# clock.net
KiCad netlist of a schematic drawn in EAGLE
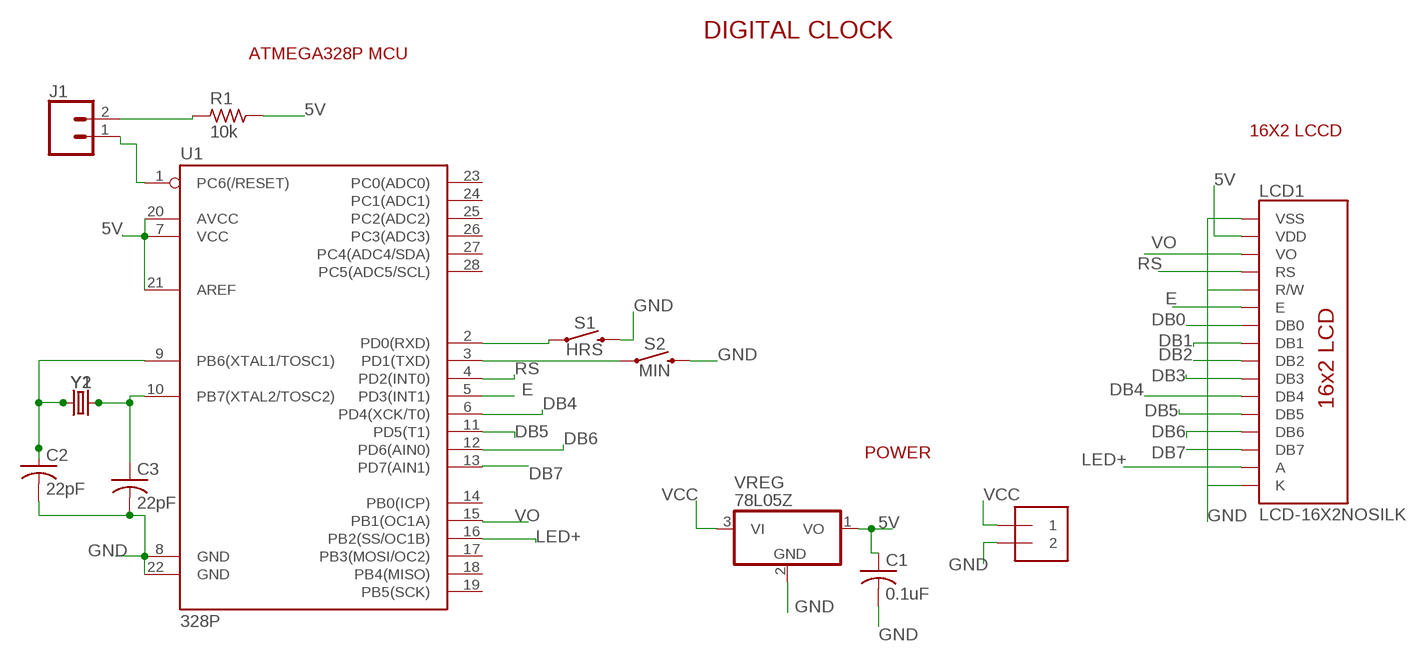
[diagram p0: schematic, sheet 1]

(export (version "E")
  (design (tool "Eeschema 10.0.6"))
  (components
    (comp (ref "C1")
      (value "0.1uF")
      (footprint "eagle-import:C1206")
      (libsource (lib "eagle-import") (part "C-USC1206"))
    )
    (comp (ref "C2")
      (value "22pF")
      (footprint "eagle-import:C1206")
      (libsource (lib "eagle-import") (part "C-USC1206"))
    )
    (comp (ref "C3")
      (value "22pF")
      (footprint "eagle-import:C1206")
      (libsource (lib "eagle-import") (part "C-USC1206"))
    )
    (comp (ref "J1")
      (value "CONN_02")
      (footprint "eagle-import:1X02")
      (libsource (lib "eagle-import") (part "CONN_02"))
    )
    (comp (ref "LCD1")
      (value "LCD-16X2NOSILK")
      (footprint "eagle-import:LCD-16X2_NOSILK")
      (libsource (lib "eagle-import") (part "LCD-16X2NOSILK"))
    )
    (comp (ref "POWER")
      (value "1X2-3.5MM")
      (footprint "eagle-import:1X2-3.5MM")
      (libsource (lib "eagle-import") (part "1X2-3.5MM"))
    )
    (comp (ref "R1")
      (value "10k")
      (footprint "eagle-import:R1206")
      (libsource (lib "eagle-import") (part "R_1206"))
    )
    (comp (ref "S1")
      (value "HRS")
      (footprint "eagle-import:TACTILE_SWITCH_PTH_6.0MM")
      (libsource (lib "eagle-import") (part "MOMENTARY-SWITCH-SPST-PTH-6.0MM"))
    )
    (comp (ref "S2")
      (value "MIN")
      (footprint "eagle-import:TACTILE_SWITCH_PTH_6.0MM")
      (libsource (lib "eagle-import") (part "MOMENTARY-SWITCH-SPST-PTH-6.0MM"))
    )
    (comp (ref "U1")
      (value "328P")
      (footprint "eagle-import:DIP28")
      (libsource (lib "eagle-import") (part "ATMEGA328P_PDIP"))
    )
    (comp (ref "VREG")
      (value "78L05Z")
      (footprint "eagle-import:TO92")
      (libsource (lib "eagle-import") (part "78ZL05"))
    )
    (comp (ref "Y1")
      (value "CRYSTALPTH-HC49US")
      (footprint "eagle-import:HC49US")
      (libsource (lib "eagle-import") (part "CRYSTALPTH-HC49US"))
    )
    (comp (ref "Y2")
      (value "CRYSTALPTH-HC49US")
      (footprint "eagle-import:HC49US")
      (libsource (lib "eagle-import") (part "CRYSTALPTH-HC49US"))
    )
  )
  (nets
    (net (code "1") (name "/5V") (class "Default")
      (node (ref "C1") (pin "1") (pinfunction "1_1") (pintype "passive"))
      (node (ref "LCD1") (pin "2") (pinfunction "VDD_2") (pintype "power_in"))
      (node (ref "R1") (pin "2") (pinfunction "2_2") (pintype "passive"))
      (node (ref "U1") (pin "20") (pinfunction "AVCC_20") (pintype "bidirectional"))
      (node (ref "U1") (pin "21") (pinfunction "AREF_21") (pintype "bidirectional"))
      (node (ref "U1") (pin "7") (pinfunction "VCC_7") (pintype "bidirectional"))
      (node (ref "VREG") (pin "1") (pinfunction "VO_1") (pintype "passive"))
    )
    (net (code "2") (name "/DB0") (class "Default")
      (node (ref "LCD1") (pin "7") (pinfunction "DB0_7") (pintype "bidirectional"))
    )
    (net (code "3") (name "/DB1") (class "Default")
      (node (ref "LCD1") (pin "8") (pinfunction "DB1_8") (pintype "bidirectional"))
    )
    (net (code "4") (name "/DB2") (class "Default")
      (node (ref "LCD1") (pin "9") (pinfunction "DB2_9") (pintype "bidirectional"))
    )
    (net (code "5") (name "/DB3") (class "Default")
      (node (ref "LCD1") (pin "10") (pinfunction "DB3_10") (pintype "bidirectional"))
    )
    (net (code "6") (name "/DB4") (class "Default")
      (node (ref "LCD1") (pin "11") (pinfunction "DB4_11") (pintype "bidirectional"))
      (node (ref "U1") (pin "6") (pinfunction "PD4(XCK/T0)_6") (pintype "bidirectional"))
    )
    (net (code "7") (name "/DB5") (class "Default")
      (node (ref "LCD1") (pin "12") (pinfunction "DB5_12") (pintype "bidirectional"))
      (node (ref "U1") (pin "11") (pinfunction "PD5(T1)_11") (pintype "bidirectional"))
    )
    (net (code "8") (name "/DB6") (class "Default")
      (node (ref "LCD1") (pin "13") (pinfunction "DB6_13") (pintype "bidirectional"))
      (node (ref "U1") (pin "12") (pinfunction "PD6(AIN0)_12") (pintype "bidirectional"))
    )
    (net (code "9") (name "/DB7") (class "Default")
      (node (ref "LCD1") (pin "14") (pinfunction "DB7_14") (pintype "bidirectional"))
      (node (ref "U1") (pin "13") (pinfunction "PD7(AIN1)_13") (pintype "bidirectional"))
    )
    (net (code "10") (name "/E") (class "Default")
      (node (ref "LCD1") (pin "6") (pinfunction "E_6") (pintype "input"))
      (node (ref "U1") (pin "5") (pinfunction "PD3(INT1)_5") (pintype "bidirectional"))
    )
    (net (code "11") (name "/GND") (class "Default")
      (node (ref "C1") (pin "2") (pinfunction "2_2") (pintype "passive"))
      (node (ref "C2") (pin "1") (pinfunction "1_1") (pintype "passive"))
      (node (ref "C2") (pin "2") (pinfunction "2_2") (pintype "passive"))
      (node (ref "C3") (pin "2") (pinfunction "2_2") (pintype "passive"))
      (node (ref "LCD1") (pin "16") (pinfunction "K_16") (pintype "power_in"))
      (node (ref "POWER") (pin "2") (pinfunction "2_2") (pintype "passive"))
      (node (ref "S1") (pin "3") (pinfunction "2_3") (pintype "passive"))
      (node (ref "S2") (pin "3") (pinfunction "2_3") (pintype "passive"))
      (node (ref "U1") (pin "22") (pinfunction "GND_22") (pintype "bidirectional"))
      (node (ref "U1") (pin "8") (pinfunction "GND_8") (pintype "bidirectional"))
      (node (ref "U1") (pin "9") (pinfunction "PB6(XTAL1/TOSC1)_9") (pintype "bidirectional"))
      (node (ref "VREG") (pin "2") (pinfunction "GND_2") (pintype "passive"))
      (node (ref "Y1") (pin "1") (pinfunction "1_1") (pintype "passive"))
      (node (ref "Y2") (pin "1") (pinfunction "1_1") (pintype "passive"))
    )
    (net (code "12") (name "/LED+") (class "Default")
      (node (ref "LCD1") (pin "15") (pinfunction "A_15") (pintype "power_in"))
      (node (ref "U1") (pin "16") (pinfunction "PB2(SS/OC1B)_16") (pintype "bidirectional"))
    )
    (net (code "13") (name "/RS") (class "Default")
      (node (ref "LCD1") (pin "4") (pinfunction "RS_4") (pintype "input"))
      (node (ref "U1") (pin "4") (pinfunction "PD2(INT0)_4") (pintype "bidirectional"))
    )
    (net (code "14") (name "/VCC") (class "Default")
      (node (ref "POWER") (pin "1") (pinfunction "1_1") (pintype "passive"))
      (node (ref "VREG") (pin "3") (pinfunction "VI_3") (pintype "input"))
    )
    (net (code "15") (name "/VO") (class "Default")
      (node (ref "LCD1") (pin "3") (pinfunction "VO_3") (pintype "bidirectional"))
      (node (ref "U1") (pin "15") (pinfunction "PB1(OC1A)_15") (pintype "bidirectional"))
    )
    (net (code "16") (name "Net-(J1-Pad2)") (class "Default")
      (node (ref "J1") (pin "2") (pinfunction "2_2") (pintype "passive"))
      (node (ref "R1") (pin "1") (pinfunction "1_1") (pintype "passive"))
    )
    (net (code "17") (name "Net-(LCD1-R{slash}W)") (class "Default")
      (node (ref "LCD1") (pin "1") (pinfunction "VSS_1") (pintype "power_in"))
      (node (ref "LCD1") (pin "5") (pinfunction "R/W_5") (pintype "input"))
    )
    (net (code "18") (name "Net-(U1-PB7(XTAL2{slash}TOSC2))") (class "Default")
      (node (ref "C3") (pin "1") (pinfunction "1_1") (pintype "passive"))
      (node (ref "U1") (pin "10") (pinfunction "PB7(XTAL2/TOSC2)_10") (pintype "bidirectional"))
      (node (ref "Y1") (pin "2") (pinfunction "2_2") (pintype "passive"))
      (node (ref "Y2") (pin "2") (pinfunction "2_2") (pintype "passive"))
    )
    (net (code "19") (name "Net-(U1-PC6({slash}RESET))") (class "Default")
      (node (ref "J1") (pin "1") (pinfunction "1_1") (pintype "passive"))
      (node (ref "U1") (pin "1") (pinfunction "PC6(/RESET)_1") (pintype "bidirectional"))
    )
    (net (code "20") (name "Net-(U1-PD0(RXD))") (class "Default")
      (node (ref "S1") (pin "1") (pinfunction "1_1") (pintype "passive"))
      (node (ref "U1") (pin "2") (pinfunction "PD0(RXD)_2") (pintype "bidirectional"))
    )
    (net (code "21") (name "Net-(U1-PD1(TXD))") (class "Default")
      (node (ref "S2") (pin "1") (pinfunction "1_1") (pintype "passive"))
      (node (ref "U1") (pin "3") (pinfunction "PD1(TXD)_3") (pintype "bidirectional"))
    )
    (net (code "22") (name "unconnected-(U1-PB0(ICP)-Pad14)") (class "Default")
      (node (ref "U1") (pin "14") (pinfunction "PB0(ICP)_14") (pintype "bidirectional"))
    )
    (net (code "23") (name "unconnected-(U1-PB3(MOSI{slash}OC2)-Pad17)") (class "Default")
      (node (ref "U1") (pin "17") (pinfunction "PB3(MOSI/OC2)_17") (pintype "bidirectional"))
    )
    (net (code "24") (name "unconnected-(U1-PB4(MISO)-Pad18)") (class "Default")
      (node (ref "U1") (pin "18") (pinfunction "PB4(MISO)_18") (pintype "bidirectional"))
    )
    (net (code "25") (name "unconnected-(U1-PB5(SCK)-Pad19)") (class "Default")
      (node (ref "U1") (pin "19") (pinfunction "PB5(SCK)_19") (pintype "bidirectional"))
    )
    (net (code "26") (name "unconnected-(U1-PC0(ADC0)-Pad23)") (class "Default")
      (node (ref "U1") (pin "23") (pinfunction "PC0(ADC0)_23") (pintype "bidirectional"))
    )
    (net (code "27") (name "unconnected-(U1-PC1(ADC1)-Pad24)") (class "Default")
      (node (ref "U1") (pin "24") (pinfunction "PC1(ADC1)_24") (pintype "bidirectional"))
    )
    (net (code "28") (name "unconnected-(U1-PC2(ADC2)-Pad25)") (class "Default")
      (node (ref "U1") (pin "25") (pinfunction "PC2(ADC2)_25") (pintype "bidirectional"))
    )
    (net (code "29") (name "unconnected-(U1-PC3(ADC3)-Pad26)") (class "Default")
      (node (ref "U1") (pin "26") (pinfunction "PC3(ADC3)_26") (pintype "bidirectional"))
    )
    (net (code "30") (name "unconnected-(U1-PC4(ADC4{slash}SDA)-Pad27)") (class "Default")
      (node (ref "U1") (pin "27") (pinfunction "PC4(ADC4/SDA)_27") (pintype "bidirectional"))
    )
    (net (code "31") (name "unconnected-(U1-PC5(ADC5{slash}SCL)-Pad28)") (class "Default")
      (node (ref "U1") (pin "28") (pinfunction "PC5(ADC5/SCL)_28") (pintype "bidirectional"))
    )
  )
)
